# Domino_USB_MicroSD_No_Teardrop_New.net
KiCad netlist of a schematic drawn in EAGLE
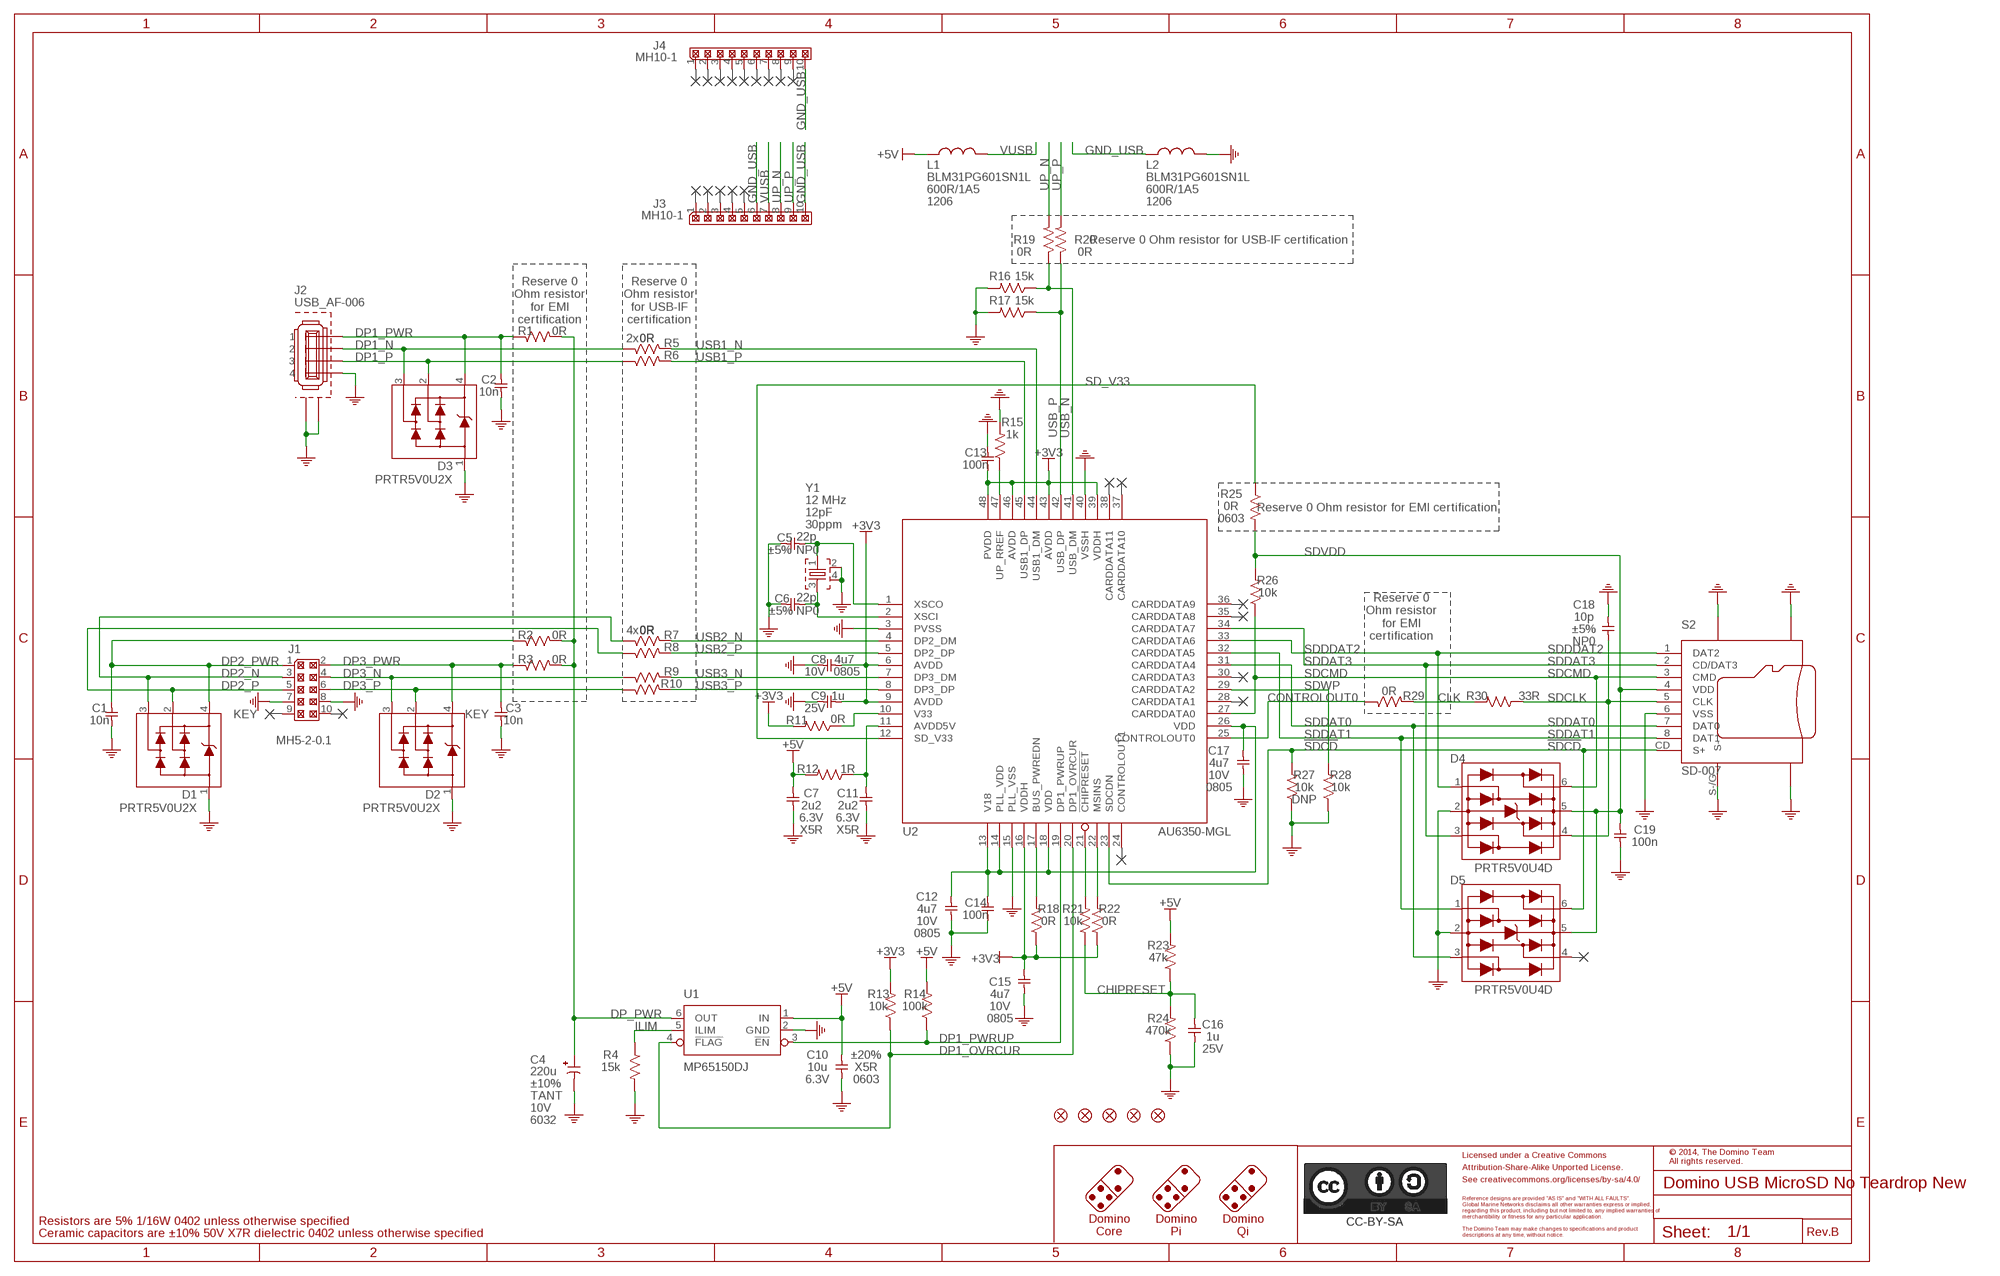
[diagram p0: schematic, sheet 1]

(export (version "E")
  (design (tool "Eeschema 10.0.6"))
  (components
    (comp (ref "C1")
      (value "10n")
      (footprint "eagle-import:C0402")
      (fields (field (name "PARTNO") "C0402_10n_X7R_10%_CER_50V"))
      (libsource (lib "eagle-import") (part "CAP_0402"))
    )
    (comp (ref "C2")
      (value "10n")
      (footprint "eagle-import:C0402")
      (fields (field (name "PARTNO") "C0402_10n_X7R_10%_CER_50V"))
      (libsource (lib "eagle-import") (part "CAP_0402"))
    )
    (comp (ref "C3")
      (value "10n")
      (footprint "eagle-import:C0402")
      (fields (field (name "PARTNO") "C0402_10n_X7R_10%_CER_50V"))
      (libsource (lib "eagle-import") (part "CAP_0402"))
    )
    (comp (ref "C4")
      (value "220u")
      (footprint "eagle-import:C_6032-25")
      (fields
        (field (name "SIZE") "6032")
        (field (name "TYPE") "TANT")
        (field (name "PARTNO") "CPOLC-6032_220u_20%_TANT_10V")
        (field (name "TOL") "±10%")
        (field (name "VOLT") "10V")
      )
      (libsource (lib "eagle-import") (part "CPOL_?C/6032-25"))
    )
    (comp (ref "C5")
      (value "22p")
      (footprint "eagle-import:C0402")
      (fields
        (field (name "PARTNO") "C0402_22p_NP0_5%_CER_50V")
        (field (name "TC") "NP0")
        (field (name "TOL") "±5%")
      )
      (libsource (lib "eagle-import") (part "CAP_0402"))
    )
    (comp (ref "C6")
      (value "22p")
      (footprint "eagle-import:C0402")
      (fields
        (field (name "PARTNO") "C0402_22p_NP0_5%_CER_50V")
        (field (name "TC") "NP0")
        (field (name "TOL") "±5%")
      )
      (libsource (lib "eagle-import") (part "CAP_0402"))
    )
    (comp (ref "C7")
      (value "2u2")
      (footprint "eagle-import:C0402")
      (fields
        (field (name "PARTNO") "C0402_2u2_X5R_10%_CER_6V3")
        (field (name "TC") "X5R")
        (field (name "VOLT") "6.3V")
      )
      (libsource (lib "eagle-import") (part "CAP_0402"))
    )
    (comp (ref "C8")
      (value "4u7")
      (footprint "eagle-import:C0805")
      (fields
        (field (name "SIZE") "0805")
        (field (name "PARTNO") "C0805_4u7_X7R_10%_CER_6V3")
        (field (name "VOLT") "10V")
      )
      (libsource (lib "eagle-import") (part "CAP_0805"))
    )
    (comp (ref "C9")
      (value "1u")
      (footprint "eagle-import:C0402")
      (fields (field (name "PARTNO") "C0402_1u_X7R_10%_CER_25V") (field (name "VOLT") "25V"))
      (libsource (lib "eagle-import") (part "CAP_0402"))
    )
    (comp (ref "C10")
      (value "10u")
      (footprint "eagle-import:C0603")
      (fields
        (field (name "SIZE") "0603")
        (field (name "PARTNO") "C0603_10u_X5R_20%_CER_6V3")
        (field (name "TC") "X5R")
        (field (name "TOL") "±20%")
        (field (name "VOLT") "6.3V")
      )
      (libsource (lib "eagle-import") (part "CAP_0603"))
    )
    (comp (ref "C11")
      (value "2u2")
      (footprint "eagle-import:C0402")
      (fields
        (field (name "PARTNO") "C0402_2u2_X5R_10%_CER_6V3")
        (field (name "TC") "X5R")
        (field (name "VOLT") "6.3V")
      )
      (libsource (lib "eagle-import") (part "CAP_0402"))
    )
    (comp (ref "C12")
      (value "4u7")
      (footprint "eagle-import:C0805")
      (fields
        (field (name "SIZE") "0805")
        (field (name "PARTNO") "C0805_4u7_X7R_10%_CER_6V3")
        (field (name "VOLT") "10V")
      )
      (libsource (lib "eagle-import") (part "CAP_0805"))
    )
    (comp (ref "C13")
      (value "100n")
      (footprint "eagle-import:C0402")
      (fields (field (name "PARTNO") "C0402_100n_X7R_10%_CER_50V"))
      (libsource (lib "eagle-import") (part "CAP_0402"))
    )
    (comp (ref "C14")
      (value "100n")
      (footprint "eagle-import:C0402")
      (fields (field (name "PARTNO") "C0402_100n_X7R_10%_CER_50V"))
      (libsource (lib "eagle-import") (part "CAP_0402"))
    )
    (comp (ref "C15")
      (value "4u7")
      (footprint "eagle-import:C0805")
      (fields
        (field (name "SIZE") "0805")
        (field (name "PARTNO") "C0805_4u7_X7R_10%_CER_6V3")
        (field (name "VOLT") "10V")
      )
      (libsource (lib "eagle-import") (part "CAP_0805"))
    )
    (comp (ref "C16")
      (value "1u")
      (footprint "eagle-import:C0402")
      (fields (field (name "PARTNO") "C0402_1u_X7R_10%_CER_25V") (field (name "VOLT") "25V"))
      (libsource (lib "eagle-import") (part "CAP_0402"))
    )
    (comp (ref "C17")
      (value "4u7")
      (footprint "eagle-import:C0805")
      (fields
        (field (name "SIZE") "0805")
        (field (name "PARTNO") "C0805_4u7_X7R_10%_CER_6V3")
        (field (name "VOLT") "10V")
      )
      (libsource (lib "eagle-import") (part "CAP_0805"))
    )
    (comp (ref "C18")
      (value "10p")
      (footprint "eagle-import:C0402")
      (fields
        (field (name "PARTNO") "C0402_10p_NP0_5%_CER_50V")
        (field (name "TC") "NP0")
        (field (name "TOL") "±5%")
      )
      (libsource (lib "eagle-import") (part "CAP_0402"))
    )
    (comp (ref "C19")
      (value "100n")
      (footprint "eagle-import:C0402")
      (fields (field (name "PARTNO") "C0402_100n_X7R_10%_CER_50V"))
      (libsource (lib "eagle-import") (part "CAP_0402"))
    )
    (comp (ref "CC-BY-SA1")
      (value "CC-BY-SA_LOGO")
      (footprint "eagle-import:CC-BY-SA_LOGO")
      (libsource (lib "eagle-import") (part "CC-BY-SA_LOGO"))
    )
    (comp (ref "D1")
      (value "PRTR5V0U2X")
      (footprint "eagle-import:SOT143B")
      (libsource (lib "eagle-import") (part "PRTR5V0U2X"))
    )
    (comp (ref "D2")
      (value "PRTR5V0U2X")
      (footprint "eagle-import:SOT143B")
      (libsource (lib "eagle-import") (part "PRTR5V0U2X"))
    )
    (comp (ref "D3")
      (value "PRTR5V0U2X")
      (footprint "eagle-import:SOT143B")
      (libsource (lib "eagle-import") (part "PRTR5V0U2X"))
    )
    (comp (ref "D4")
      (value "PRTR5V0U4D")
      (footprint "eagle-import:SOT23-6")
      (libsource (lib "eagle-import") (part "PRTR5V0U4D"))
    )
    (comp (ref "D5")
      (value "PRTR5V0U4D")
      (footprint "eagle-import:SOT23-6")
      (libsource (lib "eagle-import") (part "PRTR5V0U4D"))
    )
    (comp (ref "F1")
      (value "FIDUCIAL")
      (footprint "eagle-import:FIDUCIAL")
      (libsource (lib "eagle-import") (part "FIDUCIAL"))
    )
    (comp (ref "F2")
      (value "FIDUCIAL")
      (footprint "eagle-import:FIDUCIAL")
      (libsource (lib "eagle-import") (part "FIDUCIAL"))
    )
    (comp (ref "F4")
      (value "FIDUCIAL")
      (footprint "eagle-import:FIDUCIAL")
      (libsource (lib "eagle-import") (part "FIDUCIAL"))
    )
    (comp (ref "F5")
      (value "FIDUCIAL")
      (footprint "eagle-import:FIDUCIAL")
      (libsource (lib "eagle-import") (part "FIDUCIAL"))
    )
    (comp (ref "F6")
      (value "FIDUCIAL")
      (footprint "eagle-import:FIDUCIAL")
      (libsource (lib "eagle-import") (part "FIDUCIAL"))
    )
    (comp (ref "J1")
      (value "MH5-2-0.1")
      (footprint "eagle-import:MH05-2-0.1")
      (libsource (lib "eagle-import") (part "MH5-2"))
    )
    (comp (ref "J2")
      (value "USB_AF-006")
      (footprint "eagle-import:USB_AF-006")
      (libsource (lib "eagle-import") (part "USB_AF-006"))
    )
    (comp (ref "J3")
      (value "MH10-1")
      (footprint "eagle-import:MH10-1-0.1")
      (libsource (lib "eagle-import") (part "MH10-1"))
    )
    (comp (ref "J4")
      (value "MH10-1")
      (footprint "eagle-import:MH10-1-0.1")
      (libsource (lib "eagle-import") (part "MH10-1"))
    )
    (comp (ref "L1")
      (value "BLM31PG601SN1L")
      (footprint "eagle-import:FB1206")
      (fields (field (name "SIZE") "1206") (field (name "OPT") "600R/1A5"))
      (libsource (lib "eagle-import") (part "FB_1206"))
    )
    (comp (ref "L2")
      (value "BLM31PG601SN1L")
      (footprint "eagle-import:FB1206")
      (fields (field (name "SIZE") "1206") (field (name "OPT") "600R/1A5"))
      (libsource (lib "eagle-import") (part "FB_1206"))
    )
    (comp (ref "R1")
      (value "0R")
      (footprint "eagle-import:R0402")
      (fields (field (name "PARTNO") "R0402_0R_5%_62.5mW"))
      (libsource (lib "eagle-import") (part "RES_0402"))
    )
    (comp (ref "R2")
      (value "0R")
      (footprint "eagle-import:R0402")
      (fields (field (name "PARTNO") "R0402_0R_5%_62.5mW"))
      (libsource (lib "eagle-import") (part "RES_0402"))
    )
    (comp (ref "R3")
      (value "0R")
      (footprint "eagle-import:R0402")
      (fields (field (name "PARTNO") "R0402_0R_5%_62.5mW"))
      (libsource (lib "eagle-import") (part "RES_0402"))
    )
    (comp (ref "R4")
      (value "15k")
      (footprint "eagle-import:R0402")
      (fields (field (name "PARTNO") "R0402_15k_5%_62.5mW"))
      (libsource (lib "eagle-import") (part "RES_0402"))
    )
    (comp (ref "R5")
      (value "0R")
      (footprint "eagle-import:R0402")
      (fields (field (name "PARTNO") "R0402_0R_5%_62.5mW"))
      (libsource (lib "eagle-import") (part "RES_0402"))
    )
    (comp (ref "R6")
      (value "0R")
      (footprint "eagle-import:R0402")
      (fields (field (name "PARTNO") "R0402_0R_5%_62.5mW"))
      (libsource (lib "eagle-import") (part "RES_0402"))
    )
    (comp (ref "R7")
      (value "0R")
      (footprint "eagle-import:R0402")
      (fields (field (name "PARTNO") "R0402_0R_5%_62.5mW"))
      (libsource (lib "eagle-import") (part "RES_0402"))
    )
    (comp (ref "R8")
      (value "0R")
      (footprint "eagle-import:R0402")
      (fields (field (name "PARTNO") "R0402_0R_5%_62.5mW"))
      (libsource (lib "eagle-import") (part "RES_0402"))
    )
    (comp (ref "R9")
      (value "0R")
      (footprint "eagle-import:R0402")
      (fields (field (name "PARTNO") "R0402_0R_5%_62.5mW"))
      (libsource (lib "eagle-import") (part "RES_0402"))
    )
    (comp (ref "R10")
      (value "0R")
      (footprint "eagle-import:R0402")
      (fields (field (name "PARTNO") "R0402_0R_5%_62.5mW"))
      (libsource (lib "eagle-import") (part "RES_0402"))
    )
    (comp (ref "R11")
      (value "0R")
      (footprint "eagle-import:R0402")
      (fields (field (name "PARTNO") "R0402_0R_5%_62.5mW"))
      (libsource (lib "eagle-import") (part "RES_0402"))
    )
    (comp (ref "R12")
      (value "1R")
      (footprint "eagle-import:R0402")
      (fields (field (name "PARTNO") "R0402_1R_5%_62.5mW"))
      (libsource (lib "eagle-import") (part "RES_0402"))
    )
    (comp (ref "R13")
      (value "10k")
      (footprint "eagle-import:R0402")
      (fields (field (name "PARTNO") "R0402_10k_5%_62.5mW"))
      (libsource (lib "eagle-import") (part "RES_0402"))
    )
    (comp (ref "R14")
      (value "100k")
      (footprint "eagle-import:R0402")
      (fields (field (name "PARTNO") "R0402_100k_5%_62.5mW"))
      (libsource (lib "eagle-import") (part "RES_0402"))
    )
    (comp (ref "R15")
      (value "1k")
      (footprint "eagle-import:R0402")
      (fields (field (name "PARTNO") "R0402_1k_5%_62.5mW"))
      (libsource (lib "eagle-import") (part "RES_0402"))
    )
    (comp (ref "R16")
      (value "15k")
      (footprint "eagle-import:R0402")
      (fields (field (name "PARTNO") "R0402_15k_5%_62.5mW"))
      (libsource (lib "eagle-import") (part "RES_0402"))
    )
    (comp (ref "R17")
      (value "15k")
      (footprint "eagle-import:R0402")
      (fields (field (name "PARTNO") "R0402_15k_5%_62.5mW"))
      (libsource (lib "eagle-import") (part "RES_0402"))
    )
    (comp (ref "R18")
      (value "0R")
      (footprint "eagle-import:R0402")
      (fields (field (name "PARTNO") "R0402_0R_5%_62.5mW"))
      (libsource (lib "eagle-import") (part "RES_0402"))
    )
    (comp (ref "R19")
      (value "0R")
      (footprint "eagle-import:R0402")
      (fields (field (name "PARTNO") "R0402_0R_5%_62.5mW"))
      (libsource (lib "eagle-import") (part "RES_0402"))
    )
    (comp (ref "R20")
      (value "0R")
      (footprint "eagle-import:R0402")
      (fields (field (name "PARTNO") "R0402_0R_5%_62.5mW"))
      (libsource (lib "eagle-import") (part "RES_0402"))
    )
    (comp (ref "R21")
      (value "10k")
      (footprint "eagle-import:R0402")
      (fields (field (name "PARTNO") "R0402_10k_5%_62.5mW"))
      (libsource (lib "eagle-import") (part "RES_0402"))
    )
    (comp (ref "R22")
      (value "0R")
      (footprint "eagle-import:R0402")
      (fields (field (name "PARTNO") "R0402_0R_5%_62.5mW"))
      (libsource (lib "eagle-import") (part "RES_0402"))
    )
    (comp (ref "R23")
      (value "47k")
      (footprint "eagle-import:R0402")
      (fields (field (name "PARTNO") "R0402_47k_5%_62.5mW"))
      (libsource (lib "eagle-import") (part "RES_0402"))
    )
    (comp (ref "R24")
      (value "470k")
      (footprint "eagle-import:R0402")
      (fields (field (name "PARTNO") "R0402_470k_5%_62.5mW"))
      (libsource (lib "eagle-import") (part "RES_0402"))
    )
    (comp (ref "R25")
      (value "0R")
      (footprint "eagle-import:R0603")
      (fields (field (name "SIZE") "0603") (field (name "PARTNO") "R0603_0R_5%_125mW"))
      (libsource (lib "eagle-import") (part "RES_0603"))
    )
    (comp (ref "R26")
      (value "10k")
      (footprint "eagle-import:R0402")
      (fields (field (name "PARTNO") "R0402_10k_5%_62.5mW"))
      (libsource (lib "eagle-import") (part "RES_0402"))
    )
    (comp (ref "R27")
      (value "10k")
      (footprint "eagle-import:R0402")
      (fields (field (name "PARTNO") "R0402_10k_5%_62.5mW"))
      (libsource (lib "eagle-import") (part "RES_0402"))
    )
    (comp (ref "R28")
      (value "10k")
      (footprint "eagle-import:R0402")
      (fields (field (name "PARTNO") "R0402_10k_5%_62.5mW"))
      (libsource (lib "eagle-import") (part "RES_0402"))
    )
    (comp (ref "R29")
      (value "0R")
      (footprint "eagle-import:R0402")
      (fields (field (name "PARTNO") "R0402_0R_5%_62.5mW"))
      (libsource (lib "eagle-import") (part "RES_0402"))
    )
    (comp (ref "R30")
      (value "33R")
      (footprint "eagle-import:R0402")
      (fields (field (name "PARTNO") "R0402_33R_5%_62.5mW"))
      (libsource (lib "eagle-import") (part "RES_0402"))
    )
    (comp (ref "S2")
      (value "SD-007")
      (footprint "eagle-import:SD-007")
      (libsource (lib "eagle-import") (part "MICRO-SD"))
    )
    (comp (ref "U1")
      (value "MP65150DJ")
      (footprint "eagle-import:SOT23-6")
      (libsource (lib "eagle-import") (part "MP65150DJ"))
    )
    (comp (ref "U2")
      (value "AU6350-MGL")
      (footprint "eagle-import:LQFP-48_7X7")
      (libsource (lib "eagle-import") (part "AU6350-MGL"))
    )
    (comp (ref "Y1")
      (value "12 MHz")
      (footprint "eagle-import:CRYSTAL_32X25")
      (fields
        (field (name "LOAD") "12pF")
        (field (name "PARTNO") "CRYSTAL_32X25_2SH_12PF_30PPM")
        (field (name "TOL") "30ppm")
      )
      (libsource (lib "eagle-import") (part "CRYSTAL_2SH"))
    )
  )
  (nets
    (net (code "1") (name "+3V3") (class "Default")
      (node (ref "C13") (pin "2") (pinfunction "2_2") (pintype "passive"))
      (node (ref "C15") (pin "2") (pinfunction "2_2") (pintype "passive"))
      (node (ref "C8") (pin "2") (pinfunction "2_2") (pintype "passive"))
      (node (ref "C9") (pin "2") (pinfunction "2_2") (pintype "passive"))
      (node (ref "R11") (pin "2") (pinfunction "2_2") (pintype "passive"))
      (node (ref "R13") (pin "2") (pinfunction "2_2") (pintype "passive"))
      (node (ref "R18") (pin "1") (pinfunction "1_1") (pintype "passive"))
      (node (ref "R22") (pin "1") (pinfunction "1_1") (pintype "passive"))
      (node (ref "U2") (pin "16") (pinfunction "VDDH_16") (pintype "power_in"))
      (node (ref "U2") (pin "39") (pinfunction "VDDH_39") (pintype "power_in"))
      (node (ref "U2") (pin "43") (pinfunction "AVDD_43") (pintype "power_in"))
      (node (ref "U2") (pin "46") (pinfunction "AVDD_46") (pintype "power_in"))
      (node (ref "U2") (pin "48") (pinfunction "PVDD_48") (pintype "power_in"))
      (node (ref "U2") (pin "6") (pinfunction "AVDD_6") (pintype "power_in"))
      (node (ref "U2") (pin "9") (pinfunction "AVDD_9") (pintype "power_in"))
    )
    (net (code "2") (name "+5V") (class "Default")
      (node (ref "C10") (pin "1") (pinfunction "1_1") (pintype "passive"))
      (node (ref "C7") (pin "1") (pinfunction "1_1") (pintype "passive"))
      (node (ref "L1") (pin "2") (pinfunction "2_2") (pintype "passive"))
      (node (ref "R12") (pin "2") (pinfunction "2_2") (pintype "passive"))
      (node (ref "R14") (pin "2") (pinfunction "2_2") (pintype "passive"))
      (node (ref "R23") (pin "2") (pinfunction "2_2") (pintype "passive"))
      (node (ref "U1") (pin "1") (pinfunction "IN_1") (pintype "power_in"))
    )
    (net (code "3") (name "/CHIPRESET") (class "Default")
      (node (ref "C16") (pin "1") (pinfunction "1_1") (pintype "passive"))
      (node (ref "R21") (pin "1") (pinfunction "1_1") (pintype "passive"))
      (node (ref "R23") (pin "1") (pinfunction "1_1") (pintype "passive"))
      (node (ref "R24") (pin "2") (pinfunction "2_2") (pintype "passive"))
    )
    (net (code "4") (name "/CLK") (class "Default")
      (node (ref "R29") (pin "2") (pinfunction "2_2") (pintype "passive"))
      (node (ref "R30") (pin "2") (pinfunction "2_2") (pintype "passive"))
    )
    (net (code "5") (name "/CONTROLOUT0") (class "Default")
      (node (ref "R29") (pin "1") (pinfunction "1_1") (pintype "passive"))
      (node (ref "U2") (pin "25") (pinfunction "CONTROLOUT0_25") (pintype "output"))
    )
    (net (code "6") (name "/DP1_N") (class "Default")
      (node (ref "D3") (pin "3") (pinfunction "P$3_3") (pintype "passive"))
      (node (ref "J2") (pin "2") (pinfunction "2_2") (pintype "passive"))
      (node (ref "R5") (pin "1") (pinfunction "1_1") (pintype "passive"))
    )
    (net (code "7") (name "/DP1_OVRCUR") (class "Default")
      (node (ref "R13") (pin "1") (pinfunction "1_1") (pintype "passive"))
      (node (ref "U1") (pin "4") (pinfunction "~{FLAG}_4") (pintype "open_collector"))
      (node (ref "U2") (pin "20") (pinfunction "DP1_OVRCUR_20") (pintype "input"))
    )
    (net (code "8") (name "/DP1_P") (class "Default")
      (node (ref "D3") (pin "2") (pinfunction "P$2_2") (pintype "passive"))
      (node (ref "J2") (pin "3") (pinfunction "3_3") (pintype "passive"))
      (node (ref "R6") (pin "1") (pinfunction "1_1") (pintype "passive"))
    )
    (net (code "9") (name "/DP1_PWR") (class "Default")
      (node (ref "C2") (pin "1") (pinfunction "1_1") (pintype "passive"))
      (node (ref "D3") (pin "4") (pinfunction "P$4_4") (pintype "passive"))
      (node (ref "J2") (pin "1") (pinfunction "1_1") (pintype "passive"))
      (node (ref "R1") (pin "1") (pinfunction "1_1") (pintype "passive"))
    )
    (net (code "10") (name "/DP1_PWRUP") (class "Default")
      (node (ref "R14") (pin "1") (pinfunction "1_1") (pintype "passive"))
      (node (ref "U1") (pin "3") (pinfunction "~{EN}_3") (pintype "input"))
      (node (ref "U2") (pin "19") (pinfunction "DP1_PWRUP_19") (pintype "output"))
    )
    (net (code "11") (name "/DP2_N") (class "Default")
      (node (ref "D1") (pin "3") (pinfunction "P$3_3") (pintype "passive"))
      (node (ref "J1") (pin "3") (pinfunction "3_3") (pintype "passive"))
      (node (ref "R7") (pin "1") (pinfunction "1_1") (pintype "passive"))
    )
    (net (code "12") (name "/DP2_P") (class "Default")
      (node (ref "D1") (pin "2") (pinfunction "P$2_2") (pintype "passive"))
      (node (ref "J1") (pin "5") (pinfunction "5_5") (pintype "passive"))
      (node (ref "R8") (pin "1") (pinfunction "1_1") (pintype "passive"))
    )
    (net (code "13") (name "/DP2_PWR") (class "Default")
      (node (ref "C1") (pin "1") (pinfunction "1_1") (pintype "passive"))
      (node (ref "D1") (pin "4") (pinfunction "P$4_4") (pintype "passive"))
      (node (ref "J1") (pin "1") (pinfunction "1_1") (pintype "passive"))
      (node (ref "R2") (pin "1") (pinfunction "1_1") (pintype "passive"))
    )
    (net (code "14") (name "/DP3_N") (class "Default")
      (node (ref "D2") (pin "3") (pinfunction "P$3_3") (pintype "passive"))
      (node (ref "J1") (pin "4") (pinfunction "4_4") (pintype "passive"))
      (node (ref "R9") (pin "1") (pinfunction "1_1") (pintype "passive"))
    )
    (net (code "15") (name "/DP3_P") (class "Default")
      (node (ref "D2") (pin "2") (pinfunction "P$2_2") (pintype "passive"))
      (node (ref "J1") (pin "6") (pinfunction "6_6") (pintype "passive"))
      (node (ref "R10") (pin "1") (pinfunction "1_1") (pintype "passive"))
    )
    (net (code "16") (name "/DP3_PWR") (class "Default")
      (node (ref "C3") (pin "1") (pinfunction "1_1") (pintype "passive"))
      (node (ref "D2") (pin "4") (pinfunction "P$4_4") (pintype "passive"))
      (node (ref "J1") (pin "2") (pinfunction "2_2") (pintype "passive"))
      (node (ref "R3") (pin "1") (pinfunction "1_1") (pintype "passive"))
    )
    (net (code "17") (name "/DP_PWR") (class "Default")
      (node (ref "C4") (pin "1") (pinfunction "+_1") (pintype "passive"))
      (node (ref "R1") (pin "2") (pinfunction "2_2") (pintype "passive"))
      (node (ref "R2") (pin "2") (pinfunction "2_2") (pintype "passive"))
      (node (ref "R3") (pin "2") (pinfunction "2_2") (pintype "passive"))
      (node (ref "U1") (pin "6") (pinfunction "OUT_6") (pintype "power_in"))
    )
    (net (code "18") (name "/GND_USB") (class "Default")
      (node (ref "J3") (pin "10") (pinfunction "10_10") (pintype "passive"))
      (node (ref "J3") (pin "6") (pinfunction "6_6") (pintype "passive"))
      (node (ref "J4") (pin "10") (pinfunction "10_10") (pintype "passive"))
      (node (ref "L2") (pin "2") (pinfunction "2_2") (pintype "passive"))
    )
    (net (code "19") (name "/ILIM") (class "Default")
      (node (ref "R4") (pin "1") (pinfunction "1_1") (pintype "passive"))
      (node (ref "U1") (pin "5") (pinfunction "ILIM_5") (pintype "passive"))
    )
    (net (code "20") (name "/SDCLK") (class "Default")
      (node (ref "C18") (pin "1") (pinfunction "1_1") (pintype "passive"))
      (node (ref "D4") (pin "4") (pinfunction "I/O3_4") (pintype "passive"))
      (node (ref "R30") (pin "1") (pinfunction "1_1") (pintype "passive"))
      (node (ref "S2") (pin "5") (pinfunction "CLK_5") (pintype "input"))
    )
    (net (code "21") (name "/SDCMD") (class "Default")
      (node (ref "D4") (pin "6") (pinfunction "I/O4_6") (pintype "passive"))
      (node (ref "R26") (pin "1") (pinfunction "1_1") (pintype "passive"))
      (node (ref "S2") (pin "3") (pinfunction "CMD_3") (pintype "input"))
      (node (ref "U2") (pin "27") (pinfunction "CARDDATA0_27") (pintype "bidirectional"))
    )
    (net (code "22") (name "/SDDAT0") (class "Default")
      (node (ref "D5") (pin "3") (pinfunction "I/O2_3") (pintype "passive"))
      (node (ref "S2") (pin "7") (pinfunction "DAT0_7") (pintype "bidirectional"))
      (node (ref "U2") (pin "31") (pinfunction "CARDDATA4_31") (pintype "bidirectional"))
    )
    (net (code "23") (name "/SDDAT1") (class "Default")
      (node (ref "D5") (pin "1") (pinfunction "I/O1_1") (pintype "passive"))
      (node (ref "S2") (pin "8") (pinfunction "DAT1_8") (pintype "bidirectional"))
      (node (ref "U2") (pin "32") (pinfunction "CARDDATA5_32") (pintype "bidirectional"))
    )
    (net (code "24") (name "/SDDAT3") (class "Default")
      (node (ref "D4") (pin "3") (pinfunction "I/O2_3") (pintype "passive"))
      (node (ref "S2") (pin "2") (pinfunction "CD/DAT3_2") (pintype "bidirectional"))
      (node (ref "U2") (pin "34") (pinfunction "CARDDATA7_34") (pintype "bidirectional"))
    )
    (net (code "25") (name "/SDDDAT2") (class "Default")
      (node (ref "D4") (pin "1") (pinfunction "I/O1_1") (pintype "passive"))
      (node (ref "S2") (pin "1") (pinfunction "DAT2_1") (pintype "bidirectional"))
      (node (ref "U2") (pin "33") (pinfunction "CARDDATA6_33") (pintype "bidirectional"))
    )
    (net (code "26") (name "/SDVDD") (class "Default")
      (node (ref "C19") (pin "1") (pinfunction "1_1") (pintype "passive"))
      (node (ref "D4") (pin "5") (pinfunction "VCC_5") (pintype "passive"))
      (node (ref "D5") (pin "5") (pinfunction "VCC_5") (pintype "passive"))
      (node (ref "R25") (pin "2") (pinfunction "2_2") (pintype "passive"))
      (node (ref "R26") (pin "2") (pinfunction "2_2") (pintype "passive"))
      (node (ref "S2") (pin "4") (pinfunction "VDD_4") (pintype "power_in"))
    )
    (net (code "27") (name "/SDWP") (class "Default")
      (node (ref "R28") (pin "2") (pinfunction "2_2") (pintype "passive"))
      (node (ref "U2") (pin "29") (pinfunction "CARDDATA2_29") (pintype "bidirectional"))
    )
    (net (code "28") (name "/SD_V33") (class "Default")
      (node (ref "R25") (pin "1") (pinfunction "1_1") (pintype "passive"))
      (node (ref "U2") (pin "12") (pinfunction "SD_V33_12") (pintype "power_in"))
    )
    (net (code "29") (name "/UP_N") (class "Default")
      (node (ref "J3") (pin "8") (pinfunction "8_8") (pintype "passive"))
      (node (ref "R19") (pin "2") (pinfunction "2_2") (pintype "passive"))
    )
    (net (code "30") (name "/UP_P") (class "Default")
      (node (ref "J3") (pin "9") (pinfunction "9_9") (pintype "passive"))
      (node (ref "R20") (pin "2") (pinfunction "2_2") (pintype "passive"))
    )
    (net (code "31") (name "/USB1_N") (class "Default")
      (node (ref "R5") (pin "2") (pinfunction "2_2") (pintype "passive"))
      (node (ref "U2") (pin "44") (pinfunction "USB1_DM_44") (pintype "passive"))
    )
    (net (code "32") (name "/USB1_P") (class "Default")
      (node (ref "R6") (pin "2") (pinfunction "2_2") (pintype "passive"))
      (node (ref "U2") (pin "45") (pinfunction "USB1_DP_45") (pintype "passive"))
    )
    (net (code "33") (name "/USB2_N") (class "Default")
      (node (ref "R7") (pin "2") (pinfunction "2_2") (pintype "passive"))
      (node (ref "U2") (pin "4") (pinfunction "DP2_DM_4") (pintype "passive"))
    )
    (net (code "34") (name "/USB2_P") (class "Default")
      (node (ref "R8") (pin "2") (pinfunction "2_2") (pintype "passive"))
      (node (ref "U2") (pin "5") (pinfunction "DP2_DP_5") (pintype "passive"))
    )
    (net (code "35") (name "/USB3_N") (class "Default")
      (node (ref "R9") (pin "2") (pinfunction "2_2") (pintype "passive"))
      (node (ref "U2") (pin "7") (pinfunction "DP3_DM_7") (pintype "passive"))
    )
    (net (code "36") (name "/USB3_P") (class "Default")
      (node (ref "R10") (pin "2") (pinfunction "2_2") (pintype "passive"))
      (node (ref "U2") (pin "8") (pinfunction "DP3_DP_8") (pintype "passive"))
    )
    (net (code "37") (name "/USB_N") (class "Default")
      (node (ref "R16") (pin "1") (pinfunction "1_1") (pintype "passive"))
      (node (ref "R19") (pin "1") (pinfunction "1_1") (pintype "passive"))
      (node (ref "U2") (pin "41") (pinfunction "USB_DM_41") (pintype "passive"))
    )
    (net (code "38") (name "/USB_P") (class "Default")
      (node (ref "R17") (pin "1") (pinfunction "1_1") (pintype "passive"))
      (node (ref "R20") (pin "1") (pinfunction "1_1") (pintype "passive"))
      (node (ref "U2") (pin "42") (pinfunction "USB_DP_42") (pintype "passive"))
    )
    (net (code "39") (name "/VUSB") (class "Default")
      (node (ref "J3") (pin "7") (pinfunction "7_7") (pintype "passive"))
      (node (ref "L1") (pin "1") (pinfunction "1_1") (pintype "passive"))
    )
    (net (code "40") (name "/~{SDCD}") (class "Default")
      (node (ref "D5") (pin "6") (pinfunction "I/O4_6") (pintype "passive"))
      (node (ref "R27") (pin "2") (pinfunction "2_2") (pintype "passive"))
      (node (ref "S2") (pin "CD") (pinfunction "S+_CD") (pintype "output"))
      (node (ref "U2") (pin "23") (pinfunction "SDCDN_23") (pintype "input"))
    )
    (net (code "41") (name "GND") (class "Default")
      (node (ref "C1") (pin "2") (pinfunction "2_2") (pintype "passive"))
      (node (ref "C10") (pin "2") (pinfunction "2_2") (pintype "passive"))
      (node (ref "C11") (pin "2") (pinfunction "2_2") (pintype "passive"))
      (node (ref "C12") (pin "1") (pinfunction "1_1") (pintype "passive"))
      (node (ref "C13") (pin "1") (pinfunction "1_1") (pintype "passive"))
      (node (ref "C14") (pin "2") (pinfunction "2_2") (pintype "passive"))
      (node (ref "C15") (pin "1") (pinfunction "1_1") (pintype "passive"))
      (node (ref "C16") (pin "2") (pinfunction "2_2") (pintype "passive"))
      (node (ref "C17") (pin "1") (pinfunction "1_1") (pintype "passive"))
      (node (ref "C18") (pin "2") (pinfunction "2_2") (pintype "passive"))
      (node (ref "C19") (pin "2") (pinfunction "2_2") (pintype "passive"))
      (node (ref "C2") (pin "2") (pinfunction "2_2") (pintype "passive"))
      (node (ref "C3") (pin "2") (pinfunction "2_2") (pintype "passive"))
      (node (ref "C4") (pin "2") (pinfunction "-_2") (pintype "passive"))
      (node (ref "C5") (pin "1") (pinfunction "1_1") (pintype "passive"))
      (node (ref "C6") (pin "1") (pinfunction "1_1") (pintype "passive"))
      (node (ref "C7") (pin "2") (pinfunction "2_2") (pintype "passive"))
      (node (ref "C8") (pin "1") (pinfunction "1_1") (pintype "passive"))
      (node (ref "C9") (pin "1") (pinfunction "1_1") (pintype "passive"))
      (node (ref "D1") (pin "1") (pinfunction "P$1_1") (pintype "passive"))
      (node (ref "D2") (pin "1") (pinfunction "P$1_1") (pintype "passive"))
      (node (ref "D3") (pin "1") (pinfunction "P$1_1") (pintype "passive"))
      (node (ref "D4") (pin "2") (pinfunction "GND_2") (pintype "passive"))
      (node (ref "D5") (pin "2") (pinfunction "GND_2") (pintype "passive"))
      (node (ref "J1") (pin "7") (pinfunction "7_7") (pintype "passive"))
      (node (ref "J1") (pin "8") (pinfunction "8_8") (pintype "passive"))
      (node (ref "J2") (pin "4") (pinfunction "4_4") (pintype "passive"))
      (node (ref "J2") (pin "S$1") (pinfunction "G_S$1") (pintype "passive"))
      (node (ref "J2") (pin "S$2") (pinfunction "G_S$2") (pintype "passive"))
      (node (ref "L2") (pin "1") (pinfunction "1_1") (pintype "passive"))
      (node (ref "R15") (pin "2") (pinfunction "2_2") (pintype "passive"))
      (node (ref "R16") (pin "2") (pinfunction "2_2") (pintype "passive"))
      (node (ref "R17") (pin "2") (pinfunction "2_2") (pintype "passive"))
      (node (ref "R24") (pin "1") (pinfunction "1_1") (pintype "passive"))
      (node (ref "R27") (pin "1") (pinfunction "1_1") (pintype "passive"))
      (node (ref "R28") (pin "1") (pinfunction "1_1") (pintype "passive"))
      (node (ref "R4") (pin "2") (pinfunction "2_2") (pintype "passive"))
      (node (ref "S2") (pin "6") (pinfunction "VSS_6") (pintype "power_in"))
      (node (ref "S2") (pin "G$1") (pinfunction "G_G$1") (pintype "power_in"))
      (node (ref "S2") (pin "G$2") (pinfunction "G_G$2") (pintype "power_in"))
      (node (ref "S2") (pin "G$3") (pinfunction "G_G$3") (pintype "power_in"))
      (node (ref "S2") (pin "S-/G") (pinfunction "S-_S-/G") (pintype "power_in"))
      (node (ref "U1") (pin "2") (pinfunction "GND_2") (pintype "power_in"))
      (node (ref "U2") (pin "15") (pinfunction "PLL_VSS_15") (pintype "power_in"))
      (node (ref "U2") (pin "3") (pinfunction "PVSS_3") (pintype "power_in"))
      (node (ref "U2") (pin "40") (pinfunction "VSSH_40") (pintype "power_in"))
      (node (ref "Y1") (pin "2") (pinfunction "2_2") (pintype "passive"))
      (node (ref "Y1") (pin "4") (pinfunction "4_4") (pintype "passive"))
    )
    (net (code "42") (name "Net-(U2-AVDD5V)") (class "Default")
      (node (ref "C11") (pin "1") (pinfunction "1_1") (pintype "passive"))
      (node (ref "R12") (pin "1") (pinfunction "1_1") (pintype "passive"))
      (node (ref "U2") (pin "11") (pinfunction "AVDD5V_11") (pintype "power_in"))
    )
    (net (code "43") (name "Net-(U2-BUS_PWREDN)") (class "Default")
      (node (ref "R18") (pin "2") (pinfunction "2_2") (pintype "passive"))
      (node (ref "U2") (pin "17") (pinfunction "BUS_PWREDN_17") (pintype "input"))
    )
    (net (code "44") (name "Net-(U2-MSINS)") (class "Default")
      (node (ref "R22") (pin "2") (pinfunction "2_2") (pintype "passive"))
      (node (ref "U2") (pin "22") (pinfunction "MSINS_22") (pintype "input"))
    )
    (net (code "45") (name "Net-(U2-PLL_VDD)") (class "Default")
      (node (ref "C12") (pin "2") (pinfunction "2_2") (pintype "passive"))
      (node (ref "C14") (pin "1") (pinfunction "1_1") (pintype "passive"))
      (node (ref "C17") (pin "2") (pinfunction "2_2") (pintype "passive"))
      (node (ref "U2") (pin "13") (pinfunction "V18_13") (pintype "power_in"))
      (node (ref "U2") (pin "14") (pinfunction "PLL_VDD_14") (pintype "power_in"))
      (node (ref "U2") (pin "18") (pinfunction "VDD_18") (pintype "power_in"))
      (node (ref "U2") (pin "26") (pinfunction "VDD_26") (pintype "power_in"))
    )
    (net (code "46") (name "Net-(U2-UP_RREF)") (class "Default")
      (node (ref "R15") (pin "1") (pinfunction "1_1") (pintype "passive"))
      (node (ref "U2") (pin "47") (pinfunction "UP_RREF_47") (pintype "passive"))
    )
    (net (code "47") (name "Net-(U2-V33)") (class "Default")
      (node (ref "R11") (pin "1") (pinfunction "1_1") (pintype "passive"))
      (node (ref "U2") (pin "10") (pinfunction "V33_10") (pintype "power_in"))
    )
    (net (code "48") (name "Net-(U2-XSCI)") (class "Default")
      (node (ref "C6") (pin "2") (pinfunction "2_2") (pintype "passive"))
      (node (ref "U2") (pin "2") (pinfunction "XSCI_2") (pintype "passive"))
      (node (ref "Y1") (pin "3") (pinfunction "3_3") (pintype "passive"))
    )
    (net (code "49") (name "Net-(U2-XSCO)") (class "Default")
      (node (ref "C5") (pin "2") (pinfunction "2_2") (pintype "passive"))
      (node (ref "U2") (pin "1") (pinfunction "XSCO_1") (pintype "passive"))
      (node (ref "Y1") (pin "1") (pinfunction "1_1") (pintype "passive"))
    )
    (net (code "50") (name "Net-(U2-~{CHIPRESET})") (class "Default")
      (node (ref "R21") (pin "2") (pinfunction "2_2") (pintype "passive"))
      (node (ref "U2") (pin "21") (pinfunction "~{CHIPRESET}_21") (pintype "input"))
    )
    (net (code "51") (name "unconnected-(D5-I{slash}O3-Pad4)") (class "Default")
      (node (ref "D5") (pin "4") (pinfunction "I/O3_4") (pintype "passive"))
    )
    (net (code "52") (name "unconnected-(J1-Pad9)") (class "Default")
      (node (ref "J1") (pin "9") (pinfunction "9_9") (pintype "passive"))
    )
    (net (code "53") (name "unconnected-(J1-Pad10)") (class "Default")
      (node (ref "J1") (pin "10") (pinfunction "10_10") (pintype "passive"))
    )
    (net (code "54") (name "unconnected-(J3-Pad1)") (class "Default")
      (node (ref "J3") (pin "1") (pinfunction "1_1") (pintype "passive"))
    )
    (net (code "55") (name "unconnected-(J3-Pad2)") (class "Default")
      (node (ref "J3") (pin "2") (pinfunction "2_2") (pintype "passive"))
    )
    (net (code "56") (name "unconnected-(J3-Pad3)") (class "Default")
      (node (ref "J3") (pin "3") (pinfunction "3_3") (pintype "passive"))
    )
    (net (code "57") (name "unconnected-(J3-Pad4)") (class "Default")
      (node (ref "J3") (pin "4") (pinfunction "4_4") (pintype "passive"))
    )
    (net (code "58") (name "unconnected-(J3-Pad5)") (class "Default")
      (node (ref "J3") (pin "5") (pinfunction "5_5") (pintype "passive"))
    )
    (net (code "59") (name "unconnected-(J4-Pad1)") (class "Default")
      (node (ref "J4") (pin "1") (pinfunction "1_1") (pintype "passive"))
    )
    (net (code "60") (name "unconnected-(J4-Pad2)") (class "Default")
      (node (ref "J4") (pin "2") (pinfunction "2_2") (pintype "passive"))
    )
    (net (code "61") (name "unconnected-(J4-Pad3)") (class "Default")
      (node (ref "J4") (pin "3") (pinfunction "3_3") (pintype "passive"))
    )
    (net (code "62") (name "unconnected-(J4-Pad4)") (class "Default")
      (node (ref "J4") (pin "4") (pinfunction "4_4") (pintype "passive"))
    )
    (net (code "63") (name "unconnected-(J4-Pad5)") (class "Default")
      (node (ref "J4") (pin "5") (pinfunction "5_5") (pintype "passive"))
    )
    (net (code "64") (name "unconnected-(J4-Pad6)") (class "Default")
      (node (ref "J4") (pin "6") (pinfunction "6_6") (pintype "passive"))
    )
    (net (code "65") (name "unconnected-(J4-Pad7)") (class "Default")
      (node (ref "J4") (pin "7") (pinfunction "7_7") (pintype "passive"))
    )
    (net (code "66") (name "unconnected-(J4-Pad8)") (class "Default")
      (node (ref "J4") (pin "8") (pinfunction "8_8") (pintype "passive"))
    )
    (net (code "67") (name "unconnected-(J4-Pad9)") (class "Default")
      (node (ref "J4") (pin "9") (pinfunction "9_9") (pintype "passive"))
    )
    (net (code "68") (name "unconnected-(U2-CARDDATA1-Pad28)") (class "Default")
      (node (ref "U2") (pin "28") (pinfunction "CARDDATA1_28") (pintype "bidirectional"))
    )
    (net (code "69") (name "unconnected-(U2-CARDDATA3-Pad30)") (class "Default")
      (node (ref "U2") (pin "30") (pinfunction "CARDDATA3_30") (pintype "bidirectional"))
    )
    (net (code "70") (name "unconnected-(U2-CARDDATA8-Pad35)") (class "Default")
      (node (ref "U2") (pin "35") (pinfunction "CARDDATA8_35") (pintype "bidirectional"))
    )
    (net (code "71") (name "unconnected-(U2-CARDDATA9-Pad36)") (class "Default")
      (node (ref "U2") (pin "36") (pinfunction "CARDDATA9_36") (pintype "bidirectional"))
    )
    (net (code "72") (name "unconnected-(U2-CARDDATA10-Pad37)") (class "Default")
      (node (ref "U2") (pin "37") (pinfunction "CARDDATA10_37") (pintype "bidirectional"))
    )
    (net (code "73") (name "unconnected-(U2-CARDDATA11-Pad38)") (class "Default")
      (node (ref "U2") (pin "38") (pinfunction "CARDDATA11_38") (pintype "bidirectional"))
    )
    (net (code "74") (name "unconnected-(U2-CONTROLOUT1-Pad24)") (class "Default")
      (node (ref "U2") (pin "24") (pinfunction "CONTROLOUT1_24") (pintype "output"))
    )
  )
)
